# Data_Conversion_BottomBoard.net
KiCad netlist of a schematic drawn in Altium Designer
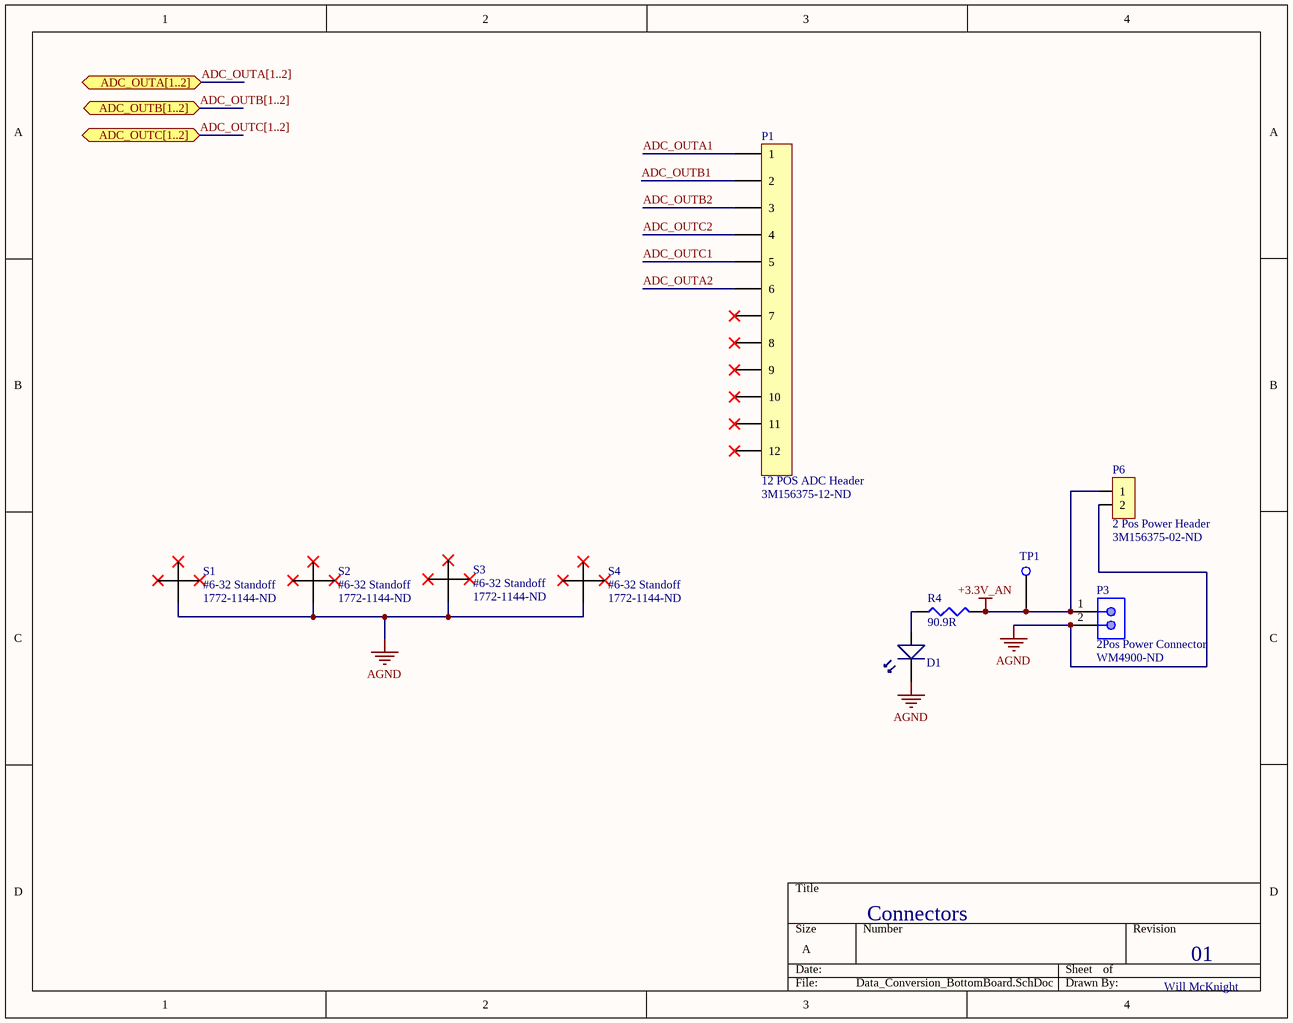
[diagram p0: Data_Conversion_BottomBoard.SchDoc]

(export (version "E")
  (design (tool "Eeschema 10.0.6"))
  (components
    (comp (ref "D1")
      (value "LED")
      (footprint "Green_SMD_LED")
      (fields
        (field (name "MANUFACTURER") "Dialight")
        (field (name "MANUFACTURER PART NUMBER") "5988070107F")
      )
      (libsource (lib "Schematic_Library") (part "GREEN_LED"))
    )
    (comp (ref "P1")
      (value "12 POS ADC Header")
      (footprint "12 POS Dual Header")
      (description "Interboard connector for thermistors connecting to ADC")
      (fields
        (field (name "MANUFACTURER") "3M")
        (field (name "MANUFACTURER PART NUMBER") "929715-06-06-EU")
        (field (name "SUPPLIER PART NUMBER 1") "3M156375-12-ND")
      )
      (libsource (lib "Schematic_Library") (part "12 POS ADC Header"))
    )
    (comp (ref "P3")
      (value "2Pos Power Connector")
      (footprint "2Pos Power Connector")
      (description "Headers & Wire Housings R/A HDR 2P low profile single")
      (fields
        (field (name "MANUFACTURER") "Molex")
        (field (name "MANUFACTURER PART NUMBER") "70553-0001")
        (field (name "SUPPLIER PART NUMBER 1") "WM4900-ND")
      )
      (libsource (lib "Schematic_Library") (part "2Pos Power Connector"))
    )
    (comp (ref "P6")
      (value "2 Pos Power Header")
      (footprint "2 POS Power Header")
      (fields
        (field (name "MANUFACTURER") "3M")
        (field (name "MANUFACTURER PART NUMBER") "929715-06-01-EU")
        (field (name "SUPPLIER PART NUMBER 1") "3M156375-02-ND")
      )
      (libsource (lib "Schematic_Library") (part "2 Pos Power Header"))
    )
    (comp (ref "R4")
      (value "Green")
      (footprint "Green_LED_Resistor_90.9")
      (fields
        (field (name "MANUFACTURER") "Panasonic")
        (field (name "MANUFACTURER PART NUMBER") "ERJ-1GNF90R9C")
        (field (name "TOLERANCE") "1%")
        (field (name "RESISTANCE") "90.9R")
      )
      (libsource (lib "Schematic_Library") (part "Green_LED_Res"))
    )
    (comp (ref "S1")
      (value "#6-32 Standoff")
      (footprint "#6-32 Stand Off")
      (description "Hex Standoff for Thermistor Boards")
      (fields
        (field (name "MANUFACTURER") "RAF")
        (field (name "MANUFACTURER PART NUMBER") "2102T-632-AL-7")
        (field (name "SUPPLIER PART NUMBER 1") "1772-1144-ND")
      )
      (libsource (lib "Schematic_Library") (part "#6-32 Standoff"))
    )
    (comp (ref "S2")
      (value "#6-32 Standoff")
      (footprint "#6-32 Stand Off")
      (description "Hex Standoff for Thermistor Boards")
      (fields
        (field (name "MANUFACTURER") "RAF")
        (field (name "MANUFACTURER PART NUMBER") "2102T-632-AL-7")
        (field (name "SUPPLIER PART NUMBER 1") "1772-1144-ND")
      )
      (libsource (lib "Schematic_Library") (part "#6-32 Standoff"))
    )
    (comp (ref "S3")
      (value "#6-32 Standoff")
      (footprint "#6-32 Stand Off")
      (description "Hex Standoff for Thermistor Boards")
      (fields
        (field (name "MANUFACTURER") "RAF")
        (field (name "MANUFACTURER PART NUMBER") "2102T-632-AL-7")
        (field (name "SUPPLIER PART NUMBER 1") "1772-1144-ND")
      )
      (libsource (lib "Schematic_Library") (part "#6-32 Standoff"))
    )
    (comp (ref "S4")
      (value "#6-32 Standoff")
      (footprint "#6-32 Stand Off")
      (description "Hex Standoff for Thermistor Boards")
      (fields
        (field (name "MANUFACTURER") "RAF")
        (field (name "MANUFACTURER PART NUMBER") "2102T-632-AL-7")
        (field (name "SUPPLIER PART NUMBER 1") "1772-1144-ND")
      )
      (libsource (lib "Schematic_Library") (part "#6-32 Standoff"))
    )
    (comp (ref "TP1")
      (value "Test Point")
      (footprint "Test Point")
      (libsource (lib "Schematic_Library") (part "Test Point"))
    )
  )
  (nets
    (net (code "1") (name "+3.3V_AN") (class "Default")
      (node (ref "P3") (pin "1") (pinfunction "1_1") (pintype "passive"))
      (node (ref "P6") (pin "1") (pinfunction "1_1") (pintype "passive"))
      (node (ref "R4") (pin "2") (pinfunction "2_2") (pintype "passive"))
      (node (ref "TP1") (pin "1") (pinfunction "1_1") (pintype "passive"))
    )
    (net (code "2") (name "/ADC_OUTA1") (class "Default")
      (node (ref "P1") (pin "1") (pinfunction "1_1") (pintype "passive"))
    )
    (net (code "3") (name "/ADC_OUTA2") (class "Default")
      (node (ref "P1") (pin "6") (pinfunction "6_6") (pintype "passive"))
    )
    (net (code "5") (name "/ADC_OUTB1") (class "Default")
      (node (ref "P1") (pin "2") (pinfunction "2_2") (pintype "passive"))
    )
    (net (code "6") (name "/ADC_OUTB2") (class "Default")
      (node (ref "P1") (pin "3") (pinfunction "3_3") (pintype "passive"))
    )
    (net (code "8") (name "/ADC_OUTC1") (class "Default")
      (node (ref "P1") (pin "5") (pinfunction "5_5") (pintype "passive"))
    )
    (net (code "9") (name "/ADC_OUTC2") (class "Default")
      (node (ref "P1") (pin "4") (pinfunction "4_4") (pintype "passive"))
    )
    (net (code "11") (name "AGND") (class "Default")
      (node (ref "D1") (pin "1") (pinfunction "1_1") (pintype "passive"))
      (node (ref "P3") (pin "2") (pinfunction "2_2") (pintype "passive"))
      (node (ref "P6") (pin "2") (pinfunction "2_2") (pintype "passive"))
      (node (ref "S1") (pin "1") (pinfunction "2_1") (pintype "passive"))
      (node (ref "S2") (pin "1") (pinfunction "2_1") (pintype "passive"))
      (node (ref "S3") (pin "1") (pinfunction "2_1") (pintype "passive"))
      (node (ref "S4") (pin "1") (pinfunction "2_1") (pintype "passive"))
    )
    (net (code "12") (name "Net-(D1-Pad2)") (class "Default")
      (node (ref "D1") (pin "2") (pinfunction "2_2") (pintype "passive"))
      (node (ref "R4") (pin "1") (pinfunction "1_1") (pintype "passive"))
    )
    (net (code "13") (name "unconnected-(P1-Pad7)") (class "Default")
      (node (ref "P1") (pin "7") (pinfunction "7_7") (pintype "passive+no_connect"))
    )
    (net (code "14") (name "unconnected-(P1-Pad8)") (class "Default")
      (node (ref "P1") (pin "8") (pinfunction "8_8") (pintype "passive+no_connect"))
    )
    (net (code "15") (name "unconnected-(P1-Pad9)") (class "Default")
      (node (ref "P1") (pin "9") (pinfunction "9_9") (pintype "passive+no_connect"))
    )
    (net (code "16") (name "unconnected-(P1-Pad10)") (class "Default")
      (node (ref "P1") (pin "10") (pinfunction "10_10") (pintype "passive+no_connect"))
    )
    (net (code "17") (name "unconnected-(P1-Pad11)") (class "Default")
      (node (ref "P1") (pin "11") (pinfunction "11_11") (pintype "passive+no_connect"))
    )
    (net (code "18") (name "unconnected-(P1-Pad12)") (class "Default")
      (node (ref "P1") (pin "12") (pinfunction "12_12") (pintype "passive+no_connect"))
    )
    (net (code "19") (name "unconnected-(S1-3-Pad1)") (class "Default")
      (node (ref "S1") (pin "1") (pinfunction "3_1") (pintype "passive+no_connect"))
    )
    (net (code "20") (name "unconnected-(S1-4-Pad1)") (class "Default")
      (node (ref "S1") (pin "1") (pinfunction "4_1") (pintype "passive+no_connect"))
    )
    (net (code "21") (name "unconnected-(S1-Pad1)") (class "Default")
      (node (ref "S1") (pin "1") (pinfunction "1_1") (pintype "passive+no_connect"))
    )
    (net (code "22") (name "unconnected-(S2-3-Pad1)") (class "Default")
      (node (ref "S2") (pin "1") (pinfunction "3_1") (pintype "passive+no_connect"))
    )
    (net (code "23") (name "unconnected-(S2-4-Pad1)") (class "Default")
      (node (ref "S2") (pin "1") (pinfunction "4_1") (pintype "passive+no_connect"))
    )
    (net (code "24") (name "unconnected-(S2-Pad1)") (class "Default")
      (node (ref "S2") (pin "1") (pinfunction "1_1") (pintype "passive+no_connect"))
    )
    (net (code "25") (name "unconnected-(S3-3-Pad1)") (class "Default")
      (node (ref "S3") (pin "1") (pinfunction "3_1") (pintype "passive+no_connect"))
    )
    (net (code "26") (name "unconnected-(S3-4-Pad1)") (class "Default")
      (node (ref "S3") (pin "1") (pinfunction "4_1") (pintype "passive+no_connect"))
    )
    (net (code "27") (name "unconnected-(S3-Pad1)") (class "Default")
      (node (ref "S3") (pin "1") (pinfunction "1_1") (pintype "passive+no_connect"))
    )
    (net (code "28") (name "unconnected-(S4-3-Pad1)") (class "Default")
      (node (ref "S4") (pin "1") (pinfunction "3_1") (pintype "passive+no_connect"))
    )
    (net (code "29") (name "unconnected-(S4-4-Pad1)") (class "Default")
      (node (ref "S4") (pin "1") (pinfunction "4_1") (pintype "passive+no_connect"))
    )
    (net (code "30") (name "unconnected-(S4-Pad1)") (class "Default")
      (node (ref "S4") (pin "1") (pinfunction "1_1") (pintype "passive+no_connect"))
    )
  )
)
